# Mithun_CEM.net
KiCad netlist of a schematic drawn in EAGLE
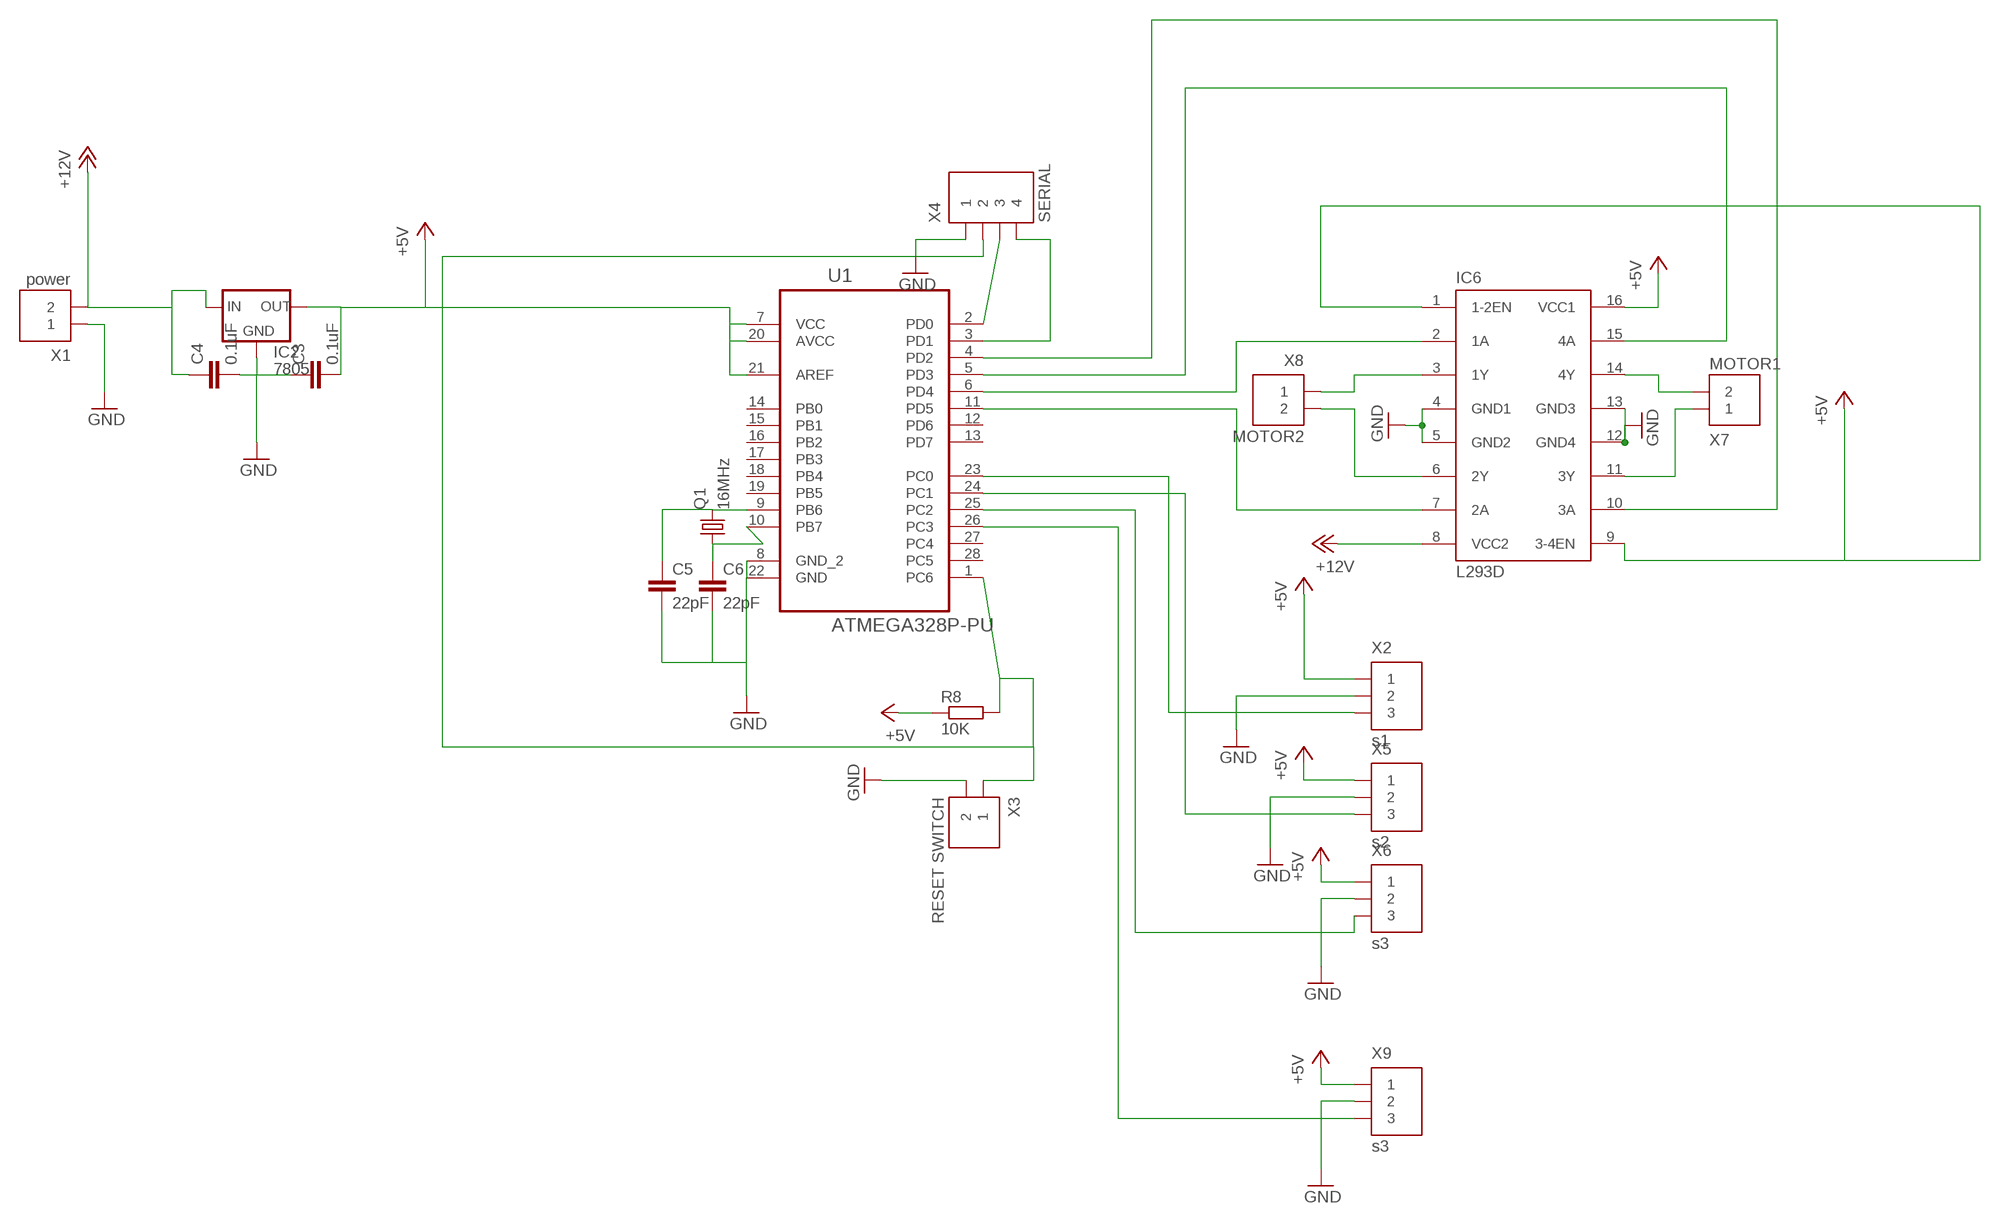
[diagram p0: schematic, sheet 1]

(export (version "E")
  (design (tool "Eeschema 10.0.6"))
  (components
    (comp (ref "C3")
      (value "0.1uF")
      (footprint "eagle-import:C050-024X044")
      (libsource (lib "eagle-import") (part "C-EU050-024X044"))
    )
    (comp (ref "C4")
      (value "0.1uF")
      (footprint "eagle-import:C050-024X044")
      (libsource (lib "eagle-import") (part "C-EU050-024X044"))
    )
    (comp (ref "C5")
      (value "22pF")
      (footprint "eagle-import:C050-024X044")
      (libsource (lib "eagle-import") (part "C-EU050-024X044"))
    )
    (comp (ref "C6")
      (value "22pF")
      (footprint "eagle-import:C050-024X044")
      (libsource (lib "eagle-import") (part "C-EU050-024X044"))
    )
    (comp (ref "IC2")
      (value "7805")
      (footprint "eagle-import:78MXXS")
      (libsource (lib "eagle-import") (part "78MXXS"))
    )
    (comp (ref "IC6")
      (value "L293D")
      (footprint "eagle-import:DIL16")
      (libsource (lib "eagle-import") (part "L293D"))
    )
    (comp (ref "Q1")
      (value "16MHz")
      (footprint "eagle-import:HC18U-V")
      (libsource (lib "eagle-import") (part "CRYSTALHC18U-V"))
    )
    (comp (ref "R8")
      (value "10K")
      (footprint "eagle-import:0204_5")
      (libsource (lib "eagle-import") (part "R-EU_0204/5"))
    )
    (comp (ref "U1")
      (value "ATMEGA328P-PU")
      (footprint "eagle-import:DIP254P762X457-28")
      (libsource (lib "eagle-import") (part "ATMEGA328P-PU"))
    )
    (comp (ref "X1")
      (value "power")
      (footprint "eagle-import:MKS1852-6-0-202")
      (fields (field (name "OC_FARNELL") "unknown") (field (name "OC_NEWARK") "unknown"))
      (libsource (lib "eagle-import") (part "MKS1852-6-0-202"))
    )
    (comp (ref "X2")
      (value "s1")
      (footprint "eagle-import:MKS1853-6-0-303")
      (libsource (lib "eagle-import") (part "MKS1853-6-0-303"))
    )
    (comp (ref "X3")
      (value "RESET SWITCH")
      (footprint "eagle-import:MKS1852-6-0-202")
      (libsource (lib "eagle-import") (part "MKS1852-6-0-202"))
    )
    (comp (ref "X4")
      (value "SERIAL")
      (footprint "eagle-import:MKS1854-6-0-404")
      (libsource (lib "eagle-import") (part "MKS1854-6-0-404"))
    )
    (comp (ref "X5")
      (value "s2")
      (footprint "eagle-import:MKS1853-6-0-303")
      (libsource (lib "eagle-import") (part "MKS1853-6-0-303"))
    )
    (comp (ref "X6")
      (value "s3")
      (footprint "eagle-import:MKS1853-6-0-303")
      (libsource (lib "eagle-import") (part "MKS1853-6-0-303"))
    )
    (comp (ref "X7")
      (value "MOTOR1")
      (footprint "eagle-import:MKS1852-6-0-202")
      (fields (field (name "OC_FARNELL") "unknown") (field (name "OC_NEWARK") "unknown"))
      (libsource (lib "eagle-import") (part "MKS1852-6-0-202"))
    )
    (comp (ref "X8")
      (value "MOTOR2")
      (footprint "eagle-import:MKS1852-6-0-202")
      (fields (field (name "OC_FARNELL") "unknown") (field (name "OC_NEWARK") "unknown"))
      (libsource (lib "eagle-import") (part "MKS1852-6-0-202"))
    )
    (comp (ref "X9")
      (value "s3")
      (footprint "eagle-import:MKS1853-6-0-303")
      (libsource (lib "eagle-import") (part "MKS1853-6-0-303"))
    )
  )
  (nets
    (net (code "1") (name "+5V") (class "Default")
      (node (ref "C3") (pin "2") (pinfunction "2_2") (pintype "passive"))
      (node (ref "IC2") (pin "OUT") (pinfunction "OUT_OUT") (pintype "passive"))
      (node (ref "IC6") (pin "1") (pinfunction "1-2EN_1") (pintype "input"))
      (node (ref "IC6") (pin "16") (pinfunction "VCC1_16") (pintype "power_in"))
      (node (ref "IC6") (pin "9") (pinfunction "3-4EN_9") (pintype "input"))
      (node (ref "R8") (pin "1") (pinfunction "1_1") (pintype "passive"))
      (node (ref "U1") (pin "20") (pinfunction "AVCC_20") (pintype "power_in"))
      (node (ref "U1") (pin "21") (pinfunction "AREF_21") (pintype "input"))
      (node (ref "U1") (pin "7") (pinfunction "VCC_7") (pintype "power_in"))
      (node (ref "X2") (pin "1") (pinfunction "1_1") (pintype "input"))
      (node (ref "X5") (pin "1") (pinfunction "1_1") (pintype "input"))
      (node (ref "X6") (pin "1") (pinfunction "1_1") (pintype "input"))
      (node (ref "X9") (pin "1") (pinfunction "1_1") (pintype "input"))
    )
    (net (code "2") (name "+12V") (class "Default")
      (node (ref "C4") (pin "1") (pinfunction "1_1") (pintype "passive"))
      (node (ref "IC2") (pin "IN") (pinfunction "IN_IN") (pintype "input"))
      (node (ref "IC6") (pin "8") (pinfunction "VCC2_8") (pintype "power_in"))
      (node (ref "X1") (pin "2") (pinfunction "2_2") (pintype "input"))
    )
    (net (code "3") (name "GND") (class "Default")
      (node (ref "C3") (pin "1") (pinfunction "1_1") (pintype "passive"))
      (node (ref "C4") (pin "2") (pinfunction "2_2") (pintype "passive"))
      (node (ref "C5") (pin "2") (pinfunction "2_2") (pintype "passive"))
      (node (ref "C6") (pin "2") (pinfunction "2_2") (pintype "passive"))
      (node (ref "IC2") (pin "GND") (pinfunction "GND_GND") (pintype "input"))
      (node (ref "IC6") (pin "12") (pinfunction "GND4_12") (pintype "power_in"))
      (node (ref "IC6") (pin "13") (pinfunction "GND3_13") (pintype "power_in"))
      (node (ref "IC6") (pin "4") (pinfunction "GND1_4") (pintype "power_in"))
      (node (ref "IC6") (pin "5") (pinfunction "GND2_5") (pintype "power_in"))
      (node (ref "U1") (pin "22") (pinfunction "GND_22") (pintype "passive"))
      (node (ref "U1") (pin "8") (pinfunction "GND_2_8") (pintype "passive"))
      (node (ref "X1") (pin "1") (pinfunction "1_1") (pintype "input"))
      (node (ref "X2") (pin "2") (pinfunction "2_2") (pintype "input"))
      (node (ref "X3") (pin "2") (pinfunction "2_2") (pintype "input"))
      (node (ref "X4") (pin "1") (pinfunction "1_1") (pintype "input"))
      (node (ref "X5") (pin "2") (pinfunction "2_2") (pintype "input"))
      (node (ref "X6") (pin "2") (pinfunction "2_2") (pintype "input"))
      (node (ref "X9") (pin "2") (pinfunction "2_2") (pintype "input"))
    )
    (net (code "4") (name "Net-(IC6-1A)") (class "Default")
      (node (ref "IC6") (pin "2") (pinfunction "1A_2") (pintype "input"))
      (node (ref "U1") (pin "6") (pinfunction "PD4_6") (pintype "bidirectional"))
    )
    (net (code "5") (name "Net-(IC6-1Y)") (class "Default")
      (node (ref "IC6") (pin "3") (pinfunction "1Y_3") (pintype "output"))
      (node (ref "X8") (pin "1") (pinfunction "1_1") (pintype "input"))
    )
    (net (code "6") (name "Net-(IC6-2A)") (class "Default")
      (node (ref "IC6") (pin "7") (pinfunction "2A_7") (pintype "input"))
      (node (ref "U1") (pin "11") (pinfunction "PD5_11") (pintype "bidirectional"))
    )
    (net (code "7") (name "Net-(IC6-2Y)") (class "Default")
      (node (ref "IC6") (pin "6") (pinfunction "2Y_6") (pintype "output"))
      (node (ref "X8") (pin "2") (pinfunction "2_2") (pintype "input"))
    )
    (net (code "8") (name "Net-(IC6-3A)") (class "Default")
      (node (ref "IC6") (pin "10") (pinfunction "3A_10") (pintype "input"))
      (node (ref "U1") (pin "4") (pinfunction "PD2_4") (pintype "bidirectional"))
    )
    (net (code "9") (name "Net-(IC6-3Y)") (class "Default")
      (node (ref "IC6") (pin "11") (pinfunction "3Y_11") (pintype "output"))
      (node (ref "X7") (pin "1") (pinfunction "1_1") (pintype "input"))
    )
    (net (code "10") (name "Net-(IC6-4A)") (class "Default")
      (node (ref "IC6") (pin "15") (pinfunction "4A_15") (pintype "input"))
      (node (ref "U1") (pin "5") (pinfunction "PD3_5") (pintype "bidirectional"))
    )
    (net (code "11") (name "Net-(IC6-4Y)") (class "Default")
      (node (ref "IC6") (pin "14") (pinfunction "4Y_14") (pintype "output"))
      (node (ref "X7") (pin "2") (pinfunction "2_2") (pintype "input"))
    )
    (net (code "12") (name "Net-(U1-PB6)") (class "Default")
      (node (ref "C5") (pin "1") (pinfunction "1_1") (pintype "passive"))
      (node (ref "Q1") (pin "2") (pinfunction "2_2") (pintype "passive"))
      (node (ref "U1") (pin "9") (pinfunction "PB6_9") (pintype "bidirectional"))
    )
    (net (code "13") (name "Net-(U1-PB7)") (class "Default")
      (node (ref "C6") (pin "1") (pinfunction "1_1") (pintype "passive"))
      (node (ref "Q1") (pin "1") (pinfunction "1_1") (pintype "passive"))
      (node (ref "U1") (pin "10") (pinfunction "PB7_10") (pintype "bidirectional"))
    )
    (net (code "14") (name "Net-(U1-PC0)") (class "Default")
      (node (ref "U1") (pin "23") (pinfunction "PC0_23") (pintype "bidirectional"))
      (node (ref "X2") (pin "3") (pinfunction "3_3") (pintype "input"))
    )
    (net (code "15") (name "Net-(U1-PC1)") (class "Default")
      (node (ref "U1") (pin "24") (pinfunction "PC1_24") (pintype "bidirectional"))
      (node (ref "X5") (pin "3") (pinfunction "3_3") (pintype "input"))
    )
    (net (code "16") (name "Net-(U1-PC2)") (class "Default")
      (node (ref "U1") (pin "25") (pinfunction "PC2_25") (pintype "bidirectional"))
      (node (ref "X6") (pin "3") (pinfunction "3_3") (pintype "input"))
    )
    (net (code "17") (name "Net-(U1-PC3)") (class "Default")
      (node (ref "U1") (pin "26") (pinfunction "PC3_26") (pintype "bidirectional"))
      (node (ref "X9") (pin "3") (pinfunction "3_3") (pintype "input"))
    )
    (net (code "18") (name "Net-(U1-PC6)") (class "Default")
      (node (ref "R8") (pin "2") (pinfunction "2_2") (pintype "passive"))
      (node (ref "U1") (pin "1") (pinfunction "PC6_1") (pintype "bidirectional"))
      (node (ref "X3") (pin "1") (pinfunction "1_1") (pintype "input"))
      (node (ref "X4") (pin "2") (pinfunction "2_2") (pintype "input"))
    )
    (net (code "19") (name "Net-(U1-PD0)") (class "Default")
      (node (ref "U1") (pin "2") (pinfunction "PD0_2") (pintype "bidirectional"))
      (node (ref "X4") (pin "3") (pinfunction "3_3") (pintype "input"))
    )
    (net (code "20") (name "Net-(U1-PD1)") (class "Default")
      (node (ref "U1") (pin "3") (pinfunction "PD1_3") (pintype "bidirectional"))
      (node (ref "X4") (pin "4") (pinfunction "4_4") (pintype "input"))
    )
    (net (code "21") (name "unconnected-(U1-PB0-Pad14)") (class "Default")
      (node (ref "U1") (pin "14") (pinfunction "PB0_14") (pintype "bidirectional"))
    )
    (net (code "22") (name "unconnected-(U1-PB1-Pad15)") (class "Default")
      (node (ref "U1") (pin "15") (pinfunction "PB1_15") (pintype "bidirectional"))
    )
    (net (code "23") (name "unconnected-(U1-PB2-Pad16)") (class "Default")
      (node (ref "U1") (pin "16") (pinfunction "PB2_16") (pintype "bidirectional"))
    )
    (net (code "24") (name "unconnected-(U1-PB3-Pad17)") (class "Default")
      (node (ref "U1") (pin "17") (pinfunction "PB3_17") (pintype "bidirectional"))
    )
    (net (code "25") (name "unconnected-(U1-PB4-Pad18)") (class "Default")
      (node (ref "U1") (pin "18") (pinfunction "PB4_18") (pintype "bidirectional"))
    )
    (net (code "26") (name "unconnected-(U1-PB5-Pad19)") (class "Default")
      (node (ref "U1") (pin "19") (pinfunction "PB5_19") (pintype "bidirectional"))
    )
    (net (code "27") (name "unconnected-(U1-PC4-Pad27)") (class "Default")
      (node (ref "U1") (pin "27") (pinfunction "PC4_27") (pintype "bidirectional"))
    )
    (net (code "28") (name "unconnected-(U1-PC5-Pad28)") (class "Default")
      (node (ref "U1") (pin "28") (pinfunction "PC5_28") (pintype "bidirectional"))
    )
    (net (code "29") (name "unconnected-(U1-PD6-Pad12)") (class "Default")
      (node (ref "U1") (pin "12") (pinfunction "PD6_12") (pintype "bidirectional"))
    )
    (net (code "30") (name "unconnected-(U1-PD7-Pad13)") (class "Default")
      (node (ref "U1") (pin "13") (pinfunction "PD7_13") (pintype "bidirectional"))
    )
  )
)
